# ESP32_S2_SOLO_2.net
KiCad netlist of a schematic drawn in Altium Designer
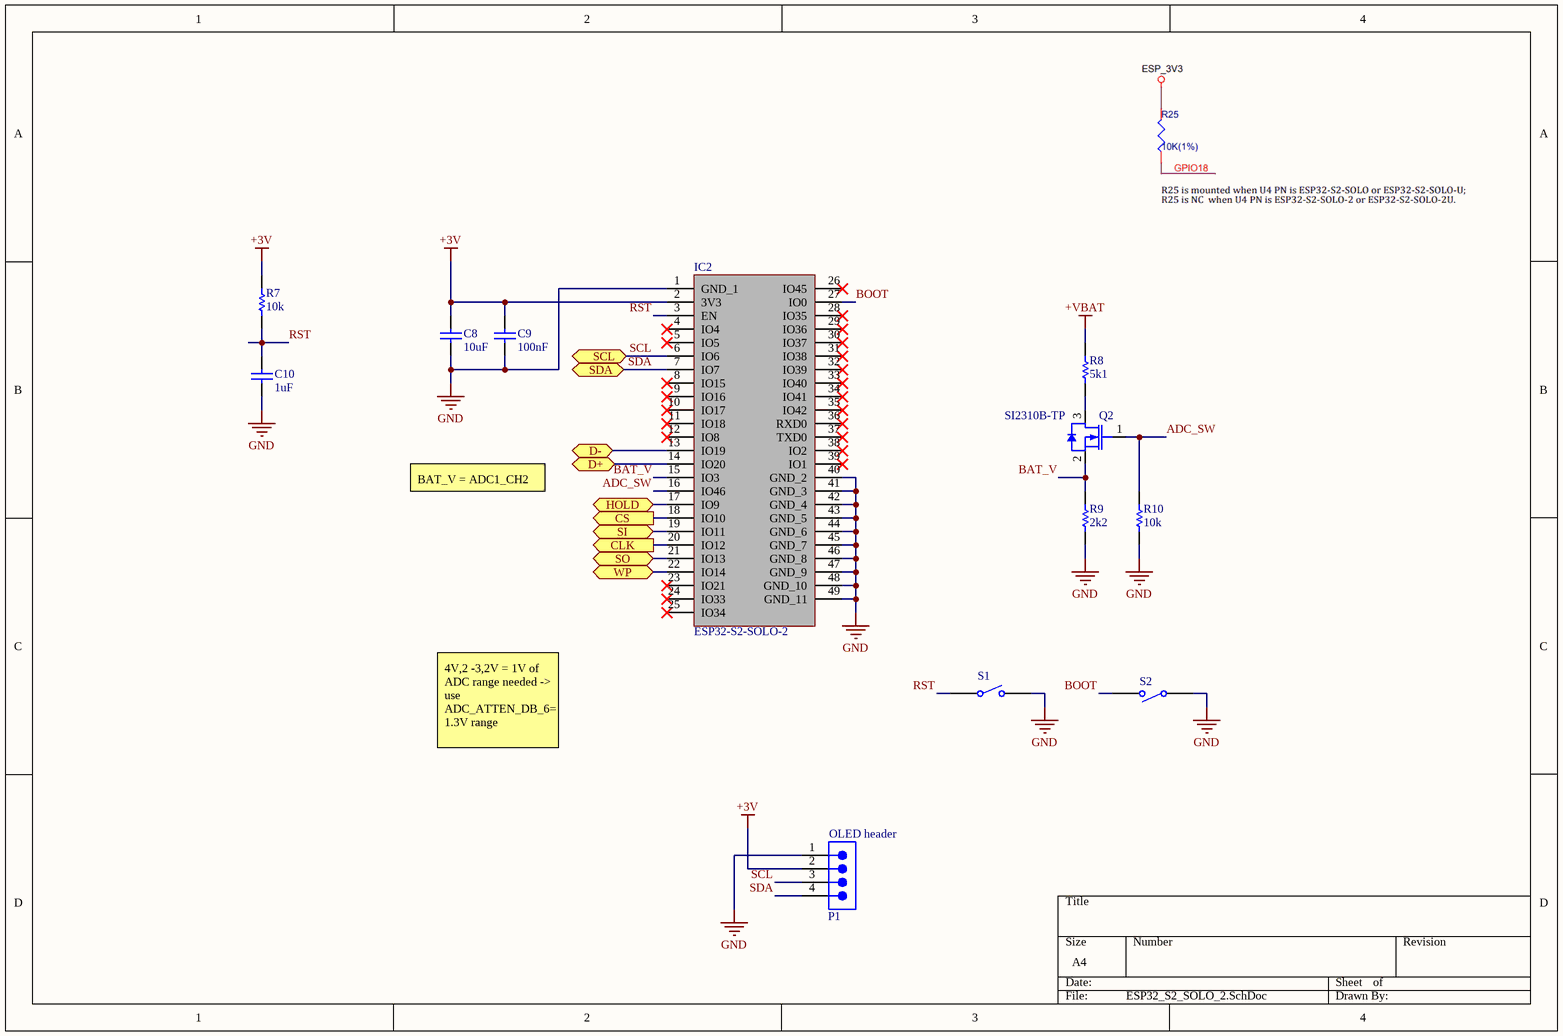
[diagram p0: ESP32_S2_SOLO_2.SchDoc]

(export (version "E")
  (design (tool "Eeschema 10.0.6"))
  (components
    (comp (ref "C8")
      (value "10uF")
      (footprint "Wurth 0603 capacitor")
      (fields (field (name "Comment") "Generic Capacitor 10uF 0603"))
      (libsource (lib "Passives") (part "Generic Capacitor 10uF 0603"))
    )
    (comp (ref "C9")
      (value "100nF")
      (footprint "Wurth 0603 capacitor")
      (fields (field (name "Comment") "Generic Capacitor 100nF 0603"))
      (libsource (lib "Passives") (part "Generic Capacitor 100nF 0603"))
    )
    (comp (ref "C10")
      (value "1uF")
      (footprint "Wurth 0603 capacitor")
      (fields (field (name "Comment") "Generic Capacitor 1uF 0603"))
      (libsource (lib "Passives") (part "Generic Capacitor 1uF 0603"))
    )
    (comp (ref "IC2")
      (value "ESP32-S2-SOLO-2")
      (footprint "ESPRESSIF ESP32S2SOLO2")
      (description "Integrated Circuit")
      (libsource (lib "MCU's") (part "Espressif ESP32-S2-SOLO-2"))
    )
    (comp (ref "P1")
      (value "OLED header")
      (footprint "4x1 2.54mm F")
      (description "WR-PHD Pin Header, THT, Vertical, pitch 2.54mm, 1 Row, 4P")
      (fields
        (field (name "MANUFACTURER PART NUMBER") "61300411121")
        (field (name "MANUFACTURER") "Wurth Elektronik")
      )
      (libsource (lib "2.54mm_pin_headers") (part "4P"))
    )
    (comp (ref "Q2")
      (value "SI2310B-TP")
      (footprint "MCC SOT-23-3")
      (description "Power Field-Effect Transistor")
      (fields (field (name "MANUFACTURER") "MCC"))
      (libsource (lib "N CHN FET") (part "MCC SI2310B-TP"))
    )
    (comp (ref "R7")
      (value "10k")
      (footprint "Wurth 0603 Resistor")
      (fields (field (name "Comment") "Generic Resistor 10k 0603"))
      (libsource (lib "Passives") (part "Generic Resistor 10k 0603"))
    )
    (comp (ref "R8")
      (value "5k1")
      (footprint "0805 Resistor")
      (fields (field (name "Comment") "Generic Resistor 5k1 0805"))
      (libsource (lib "Passives") (part "Generic Resistor 5k1 0805"))
    )
    (comp (ref "R9")
      (value "2k2")
      (footprint "Wurth 0603 Resistor")
      (fields (field (name "Comment") "Generic Resistor 2k2 0603"))
      (libsource (lib "Passives") (part "Generic Resistor 2k2 0603"))
    )
    (comp (ref "R10")
      (value "10k")
      (footprint "Wurth 0603 Resistor")
      (fields (field (name "Comment") "Generic Resistor 10k 0603"))
      (libsource (lib "Passives") (part "Generic Resistor 10k 0603"))
    )
    (comp (ref "S1")
      (value "TS-1088R-02026")
      (footprint "TS1088R02026")
      (libsource (lib "Switches") (part "XUNPU TS-1088R-02026"))
    )
    (comp (ref "S2")
      (value "TS-1088R-02026")
      (footprint "TS1088R02026")
      (libsource (lib "Switches") (part "XUNPU TS-1088R-02026"))
    )
  )
  (nets
    (net (code "1") (name "+3V") (class "Default")
      (node (ref "C8") (pin "2") (pinfunction "2_2") (pintype "passive"))
      (node (ref "C9") (pin "2") (pinfunction "2_2") (pintype "passive"))
      (node (ref "IC2") (pin "2") (pinfunction "3V3_2") (pintype "passive"))
      (node (ref "P1") (pin "2") (pinfunction "2_2") (pintype "passive"))
      (node (ref "R7") (pin "2") (pinfunction "2_2") (pintype "passive"))
    )
    (net (code "2") (name "+VBAT") (class "Default")
      (node (ref "R8") (pin "2") (pinfunction "2_2") (pintype "passive"))
    )
    (net (code "3") (name "/ADC_SW") (class "Default")
      (node (ref "IC2") (pin "16") (pinfunction "IO46_16") (pintype "passive"))
      (node (ref "Q2") (pin "1") (pinfunction "G_1") (pintype "passive"))
      (node (ref "R10") (pin "2") (pinfunction "2_2") (pintype "passive"))
    )
    (net (code "4") (name "/BAT_V") (class "Default")
      (node (ref "IC2") (pin "15") (pinfunction "IO3_15") (pintype "passive"))
      (node (ref "Q2") (pin "2") (pinfunction "S_2") (pintype "passive"))
      (node (ref "R9") (pin "2") (pinfunction "2_2") (pintype "passive"))
    )
    (net (code "5") (name "/BOOT") (class "Default")
      (node (ref "IC2") (pin "27") (pinfunction "IO0_27") (pintype "passive"))
      (node (ref "S2") (pin "2") (pinfunction "2_2") (pintype "passive"))
    )
    (net (code "6") (name "/CLK") (class "Default")
      (node (ref "IC2") (pin "20") (pinfunction "IO12_20") (pintype "passive"))
    )
    (net (code "7") (name "/CS") (class "Default")
      (node (ref "IC2") (pin "18") (pinfunction "IO10_18") (pintype "passive"))
    )
    (net (code "8") (name "/D+") (class "Default")
      (node (ref "IC2") (pin "14") (pinfunction "IO20_14") (pintype "passive"))
    )
    (net (code "9") (name "/D-") (class "Default")
      (node (ref "IC2") (pin "13") (pinfunction "IO19_13") (pintype "passive"))
    )
    (net (code "10") (name "/HOLD") (class "Default")
      (node (ref "IC2") (pin "17") (pinfunction "IO9_17") (pintype "passive"))
    )
    (net (code "11") (name "/RST") (class "Default")
      (node (ref "C10") (pin "2") (pinfunction "2_2") (pintype "passive"))
      (node (ref "IC2") (pin "3") (pinfunction "EN_3") (pintype "passive"))
      (node (ref "R7") (pin "1") (pinfunction "1_1") (pintype "passive"))
      (node (ref "S1") (pin "1") (pinfunction "1_1") (pintype "passive"))
    )
    (net (code "12") (name "/SCL") (class "Default")
      (node (ref "IC2") (pin "6") (pinfunction "IO6_6") (pintype "passive"))
      (node (ref "P1") (pin "3") (pinfunction "3_3") (pintype "passive"))
    )
    (net (code "13") (name "/SDA") (class "Default")
      (node (ref "IC2") (pin "7") (pinfunction "IO7_7") (pintype "passive"))
      (node (ref "P1") (pin "4") (pinfunction "4_4") (pintype "passive"))
    )
    (net (code "14") (name "/SI") (class "Default")
      (node (ref "IC2") (pin "19") (pinfunction "IO11_19") (pintype "passive"))
    )
    (net (code "15") (name "/SO") (class "Default")
      (node (ref "IC2") (pin "21") (pinfunction "IO13_21") (pintype "passive"))
    )
    (net (code "16") (name "/WP") (class "Default")
      (node (ref "IC2") (pin "22") (pinfunction "IO14_22") (pintype "passive"))
    )
    (net (code "17") (name "GND") (class "Default")
      (node (ref "C10") (pin "1") (pinfunction "1_1") (pintype "passive"))
      (node (ref "C8") (pin "1") (pinfunction "1_1") (pintype "passive"))
      (node (ref "C9") (pin "1") (pinfunction "1_1") (pintype "passive"))
      (node (ref "IC2") (pin "1") (pinfunction "GND_1_1") (pintype "passive"))
      (node (ref "IC2") (pin "40") (pinfunction "GND_2_40") (pintype "passive"))
      (node (ref "IC2") (pin "41") (pinfunction "GND_3_41") (pintype "passive"))
      (node (ref "IC2") (pin "42") (pinfunction "GND_4_42") (pintype "passive"))
      (node (ref "IC2") (pin "43") (pinfunction "GND_5_43") (pintype "passive"))
      (node (ref "IC2") (pin "44") (pinfunction "GND_6_44") (pintype "passive"))
      (node (ref "IC2") (pin "45") (pinfunction "GND_7_45") (pintype "passive"))
      (node (ref "IC2") (pin "46") (pinfunction "GND_8_46") (pintype "passive"))
      (node (ref "IC2") (pin "47") (pinfunction "GND_9_47") (pintype "passive"))
      (node (ref "IC2") (pin "48") (pinfunction "GND_10_48") (pintype "passive"))
      (node (ref "IC2") (pin "49") (pinfunction "GND_11_49") (pintype "passive"))
      (node (ref "P1") (pin "1") (pinfunction "1_1") (pintype "passive"))
      (node (ref "R10") (pin "1") (pinfunction "1_1") (pintype "passive"))
      (node (ref "R9") (pin "1") (pinfunction "1_1") (pintype "passive"))
      (node (ref "S1") (pin "2") (pinfunction "2_2") (pintype "passive"))
      (node (ref "S2") (pin "1") (pinfunction "1_1") (pintype "passive"))
    )
    (net (code "18") (name "Net-(Q2-D)") (class "Default")
      (node (ref "Q2") (pin "3") (pinfunction "D_3") (pintype "passive"))
      (node (ref "R8") (pin "1") (pinfunction "1_1") (pintype "passive"))
    )
    (net (code "19") (name "unconnected-(IC2-IO1-Pad39)") (class "Default")
      (node (ref "IC2") (pin "39") (pinfunction "IO1_39") (pintype "passive+no_connect"))
    )
    (net (code "20") (name "unconnected-(IC2-IO2-Pad38)") (class "Default")
      (node (ref "IC2") (pin "38") (pinfunction "IO2_38") (pintype "passive+no_connect"))
    )
    (net (code "21") (name "unconnected-(IC2-IO4-Pad4)") (class "Default")
      (node (ref "IC2") (pin "4") (pinfunction "IO4_4") (pintype "passive+no_connect"))
    )
    (net (code "22") (name "unconnected-(IC2-IO5-Pad5)") (class "Default")
      (node (ref "IC2") (pin "5") (pinfunction "IO5_5") (pintype "passive+no_connect"))
    )
    (net (code "23") (name "unconnected-(IC2-IO8-Pad12)") (class "Default")
      (node (ref "IC2") (pin "12") (pinfunction "IO8_12") (pintype "passive+no_connect"))
    )
    (net (code "24") (name "unconnected-(IC2-IO15-Pad8)") (class "Default")
      (node (ref "IC2") (pin "8") (pinfunction "IO15_8") (pintype "passive+no_connect"))
    )
    (net (code "25") (name "unconnected-(IC2-IO16-Pad9)") (class "Default")
      (node (ref "IC2") (pin "9") (pinfunction "IO16_9") (pintype "passive+no_connect"))
    )
    (net (code "26") (name "unconnected-(IC2-IO17-Pad10)") (class "Default")
      (node (ref "IC2") (pin "10") (pinfunction "IO17_10") (pintype "passive+no_connect"))
    )
    (net (code "27") (name "unconnected-(IC2-IO18-Pad11)") (class "Default")
      (node (ref "IC2") (pin "11") (pinfunction "IO18_11") (pintype "passive+no_connect"))
    )
    (net (code "28") (name "unconnected-(IC2-IO21-Pad23)") (class "Default")
      (node (ref "IC2") (pin "23") (pinfunction "IO21_23") (pintype "passive+no_connect"))
    )
    (net (code "29") (name "unconnected-(IC2-IO33-Pad24)") (class "Default")
      (node (ref "IC2") (pin "24") (pinfunction "IO33_24") (pintype "passive+no_connect"))
    )
    (net (code "30") (name "unconnected-(IC2-IO34-Pad25)") (class "Default")
      (node (ref "IC2") (pin "25") (pinfunction "IO34_25") (pintype "passive+no_connect"))
    )
    (net (code "31") (name "unconnected-(IC2-IO35-Pad28)") (class "Default")
      (node (ref "IC2") (pin "28") (pinfunction "IO35_28") (pintype "passive+no_connect"))
    )
    (net (code "32") (name "unconnected-(IC2-IO36-Pad29)") (class "Default")
      (node (ref "IC2") (pin "29") (pinfunction "IO36_29") (pintype "passive+no_connect"))
    )
    (net (code "33") (name "unconnected-(IC2-IO37-Pad30)") (class "Default")
      (node (ref "IC2") (pin "30") (pinfunction "IO37_30") (pintype "passive+no_connect"))
    )
    (net (code "34") (name "unconnected-(IC2-IO38-Pad31)") (class "Default")
      (node (ref "IC2") (pin "31") (pinfunction "IO38_31") (pintype "passive+no_connect"))
    )
    (net (code "35") (name "unconnected-(IC2-IO39-Pad32)") (class "Default")
      (node (ref "IC2") (pin "32") (pinfunction "IO39_32") (pintype "passive+no_connect"))
    )
    (net (code "36") (name "unconnected-(IC2-IO40-Pad33)") (class "Default")
      (node (ref "IC2") (pin "33") (pinfunction "IO40_33") (pintype "passive+no_connect"))
    )
    (net (code "37") (name "unconnected-(IC2-IO41-Pad34)") (class "Default")
      (node (ref "IC2") (pin "34") (pinfunction "IO41_34") (pintype "passive+no_connect"))
    )
    (net (code "38") (name "unconnected-(IC2-IO42-Pad35)") (class "Default")
      (node (ref "IC2") (pin "35") (pinfunction "IO42_35") (pintype "passive+no_connect"))
    )
    (net (code "39") (name "unconnected-(IC2-IO45-Pad26)") (class "Default")
      (node (ref "IC2") (pin "26") (pinfunction "IO45_26") (pintype "passive+no_connect"))
    )
    (net (code "40") (name "unconnected-(IC2-RXD0-Pad36)") (class "Default")
      (node (ref "IC2") (pin "36") (pinfunction "RXD0_36") (pintype "passive+no_connect"))
    )
    (net (code "41") (name "unconnected-(IC2-TXD0-Pad37)") (class "Default")
      (node (ref "IC2") (pin "37") (pinfunction "TXD0_37") (pintype "passive+no_connect"))
    )
  )
)
